# Connectors.net
KiCad netlist of a schematic drawn in Altium Designer
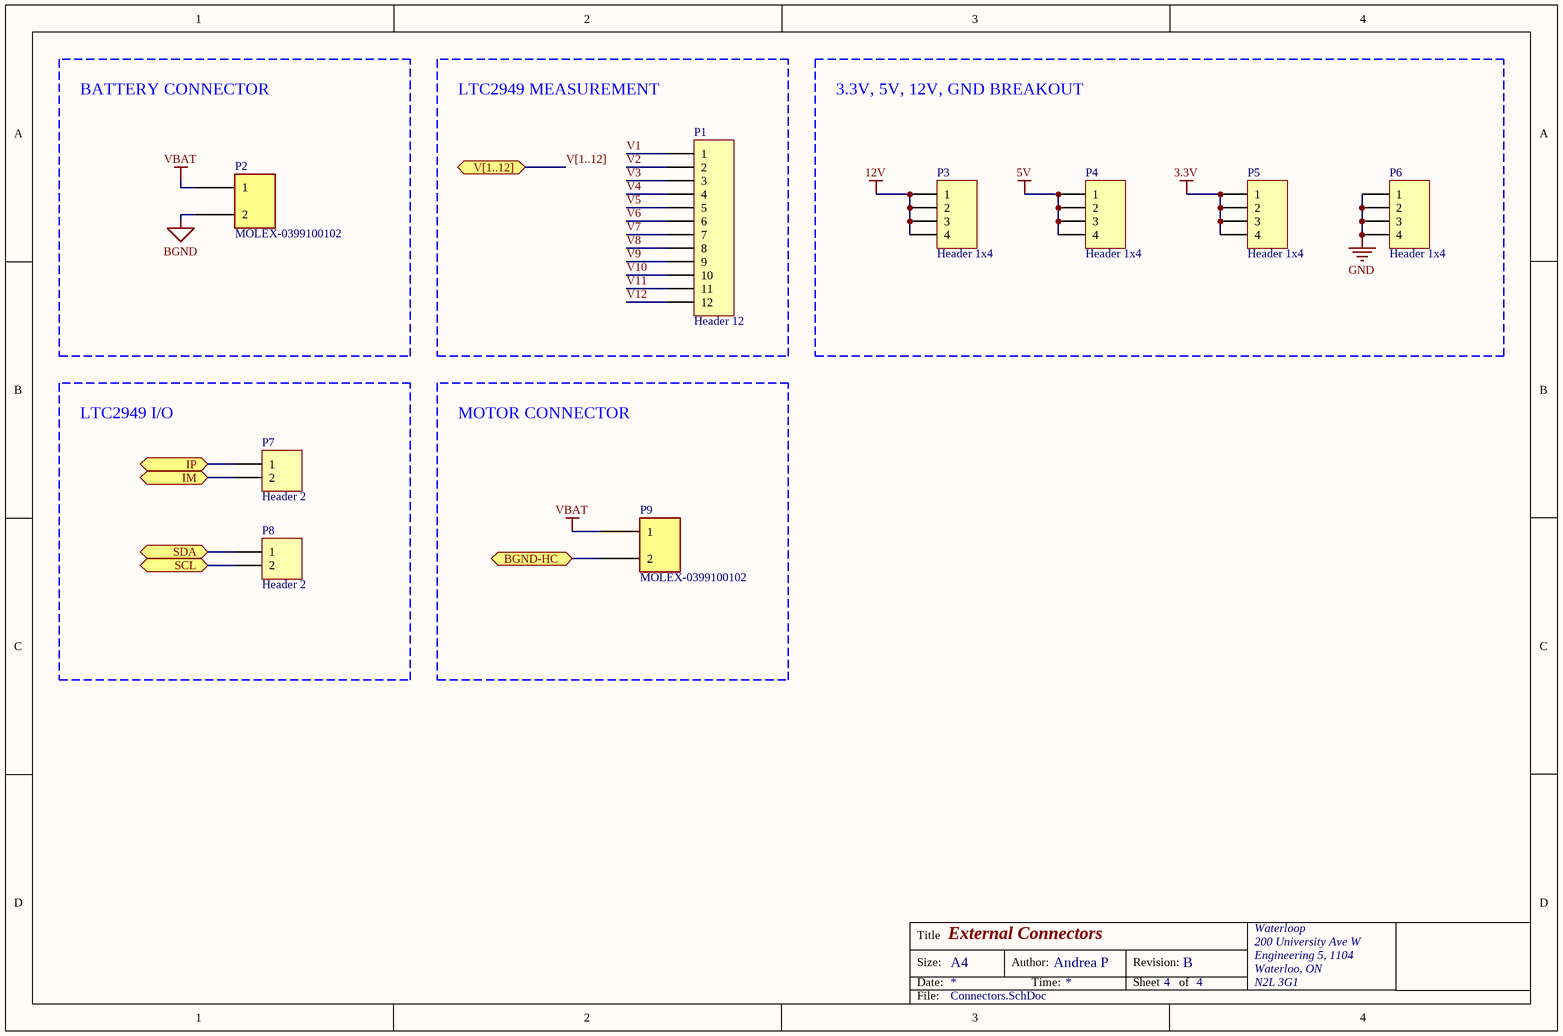
[diagram p0: Connectors.SchDoc]

(export (version "E")
  (design (tool "Eeschema 10.0.6"))
  (components
    (comp (ref "P1")
      (value "Header 12")
      (footprint "HDR1X12")
      (description "Header, 12-Pin")
      (fields (field (name "PUBLISHER") "Altium Limited"))
      (libsource (lib "Miscellaneous Connectors") (part "Header 12"))
    )
    (comp (ref "P2")
      (value "MOLEX-0399100102")
      (footprint "PHOENIX-1017531")
      (description "TERM BLK 2P SIDE ENT 10.16MM PCB")
      (libsource (lib "LTC8315") (part "MOLEX-0399100102"))
    )
    (comp (ref "P3")
      (value "Header 1x4")
      (footprint "HDR1X4")
      (description "Header, 4-Pin")
      (fields (field (name "PUBLISHER") "Altium Limited"))
      (libsource (lib "Miscellaneous Connectors") (part "Header 4"))
    )
    (comp (ref "P4")
      (value "Header 1x4")
      (footprint "HDR1X4")
      (description "Header, 4-Pin")
      (fields (field (name "PUBLISHER") "Altium Limited"))
      (libsource (lib "Miscellaneous Connectors") (part "Header 4"))
    )
    (comp (ref "P5")
      (value "Header 1x4")
      (footprint "HDR1X4")
      (description "Header, 4-Pin")
      (fields (field (name "PUBLISHER") "Altium Limited"))
      (libsource (lib "Miscellaneous Connectors") (part "Header 4"))
    )
    (comp (ref "P6")
      (value "Header 1x4")
      (footprint "HDR1X4")
      (description "Header, 4-Pin")
      (fields (field (name "PUBLISHER") "Altium Limited"))
      (libsource (lib "Miscellaneous Connectors") (part "Header 4"))
    )
    (comp (ref "P7")
      (value "Header 2")
      (footprint "HDR1X2")
      (description "Header, 2-Pin")
      (fields (field (name "PUBLISHER") "Altium Limited"))
      (libsource (lib "Miscellaneous Connectors") (part "Header 2"))
    )
    (comp (ref "P8")
      (value "Header 2")
      (footprint "HDR1X2")
      (description "Header, 2-Pin")
      (fields (field (name "PUBLISHER") "Altium Limited"))
      (libsource (lib "Miscellaneous Connectors") (part "Header 2"))
    )
    (comp (ref "P9")
      (value "MOLEX-0399100102")
      (footprint "PHOENIX-1017531")
      (description "TERM BLK 2P SIDE ENT 10.16MM PCB")
      (libsource (lib "LTC8315") (part "MOLEX-0399100102"))
    )
  )
  (nets
    (net (code "1") (name "/BGND-HC") (class "Default")
      (node (ref "P9") (pin "2") (pinfunction "2_2") (pintype "passive"))
    )
    (net (code "2") (name "/IM") (class "Default")
      (node (ref "P7") (pin "2") (pinfunction "2_2") (pintype "passive"))
    )
    (net (code "3") (name "/IP") (class "Default")
      (node (ref "P7") (pin "1") (pinfunction "1_1") (pintype "passive"))
    )
    (net (code "4") (name "/SCL") (class "Default")
      (node (ref "P8") (pin "2") (pinfunction "2_2") (pintype "passive"))
    )
    (net (code "5") (name "/SDA") (class "Default")
      (node (ref "P8") (pin "1") (pinfunction "1_1") (pintype "passive"))
    )
    (net (code "6") (name "/V1") (class "Default")
      (node (ref "P1") (pin "1") (pinfunction "1_1") (pintype "passive"))
    )
    (net (code "7") (name "/V2") (class "Default")
      (node (ref "P1") (pin "2") (pinfunction "2_2") (pintype "passive"))
    )
    (net (code "8") (name "/V3") (class "Default")
      (node (ref "P1") (pin "3") (pinfunction "3_3") (pintype "passive"))
    )
    (net (code "9") (name "/V4") (class "Default")
      (node (ref "P1") (pin "4") (pinfunction "4_4") (pintype "passive"))
    )
    (net (code "10") (name "/V5") (class "Default")
      (node (ref "P1") (pin "5") (pinfunction "5_5") (pintype "passive"))
    )
    (net (code "11") (name "/V6") (class "Default")
      (node (ref "P1") (pin "6") (pinfunction "6_6") (pintype "passive"))
    )
    (net (code "12") (name "/V7") (class "Default")
      (node (ref "P1") (pin "7") (pinfunction "7_7") (pintype "passive"))
    )
    (net (code "13") (name "/V8") (class "Default")
      (node (ref "P1") (pin "8") (pinfunction "8_8") (pintype "passive"))
    )
    (net (code "14") (name "/V9") (class "Default")
      (node (ref "P1") (pin "9") (pinfunction "9_9") (pintype "passive"))
    )
    (net (code "15") (name "/V10") (class "Default")
      (node (ref "P1") (pin "10") (pinfunction "10_10") (pintype "passive"))
    )
    (net (code "16") (name "/V11") (class "Default")
      (node (ref "P1") (pin "11") (pinfunction "11_11") (pintype "passive"))
    )
    (net (code "17") (name "/V12") (class "Default")
      (node (ref "P1") (pin "12") (pinfunction "12_12") (pintype "passive"))
    )
    (net (code "19") (name "3.3V") (class "Default")
      (node (ref "P5") (pin "1") (pinfunction "1_1") (pintype "passive"))
      (node (ref "P5") (pin "2") (pinfunction "2_2") (pintype "passive"))
      (node (ref "P5") (pin "3") (pinfunction "3_3") (pintype "passive"))
      (node (ref "P5") (pin "4") (pinfunction "4_4") (pintype "passive"))
    )
    (net (code "20") (name "5V") (class "Default")
      (node (ref "P4") (pin "1") (pinfunction "1_1") (pintype "passive"))
      (node (ref "P4") (pin "2") (pinfunction "2_2") (pintype "passive"))
      (node (ref "P4") (pin "3") (pinfunction "3_3") (pintype "passive"))
      (node (ref "P4") (pin "4") (pinfunction "4_4") (pintype "passive"))
    )
    (net (code "21") (name "12V") (class "Default")
      (node (ref "P3") (pin "1") (pinfunction "1_1") (pintype "passive"))
      (node (ref "P3") (pin "2") (pinfunction "2_2") (pintype "passive"))
      (node (ref "P3") (pin "3") (pinfunction "3_3") (pintype "passive"))
      (node (ref "P3") (pin "4") (pinfunction "4_4") (pintype "passive"))
    )
    (net (code "22") (name "BGND") (class "Default")
      (node (ref "P2") (pin "2") (pinfunction "2_2") (pintype "passive"))
    )
    (net (code "23") (name "GND") (class "Default")
      (node (ref "P6") (pin "1") (pinfunction "1_1") (pintype "passive"))
      (node (ref "P6") (pin "2") (pinfunction "2_2") (pintype "passive"))
      (node (ref "P6") (pin "3") (pinfunction "3_3") (pintype "passive"))
      (node (ref "P6") (pin "4") (pinfunction "4_4") (pintype "passive"))
    )
    (net (code "24") (name "VBAT") (class "Default")
      (node (ref "P2") (pin "1") (pinfunction "1_1") (pintype "passive"))
      (node (ref "P9") (pin "1") (pinfunction "1_1") (pintype "passive"))
    )
  )
)
